# Spannungsversorgung_V4_mitBatze.net
KiCad netlist of a schematic drawn in EAGLE
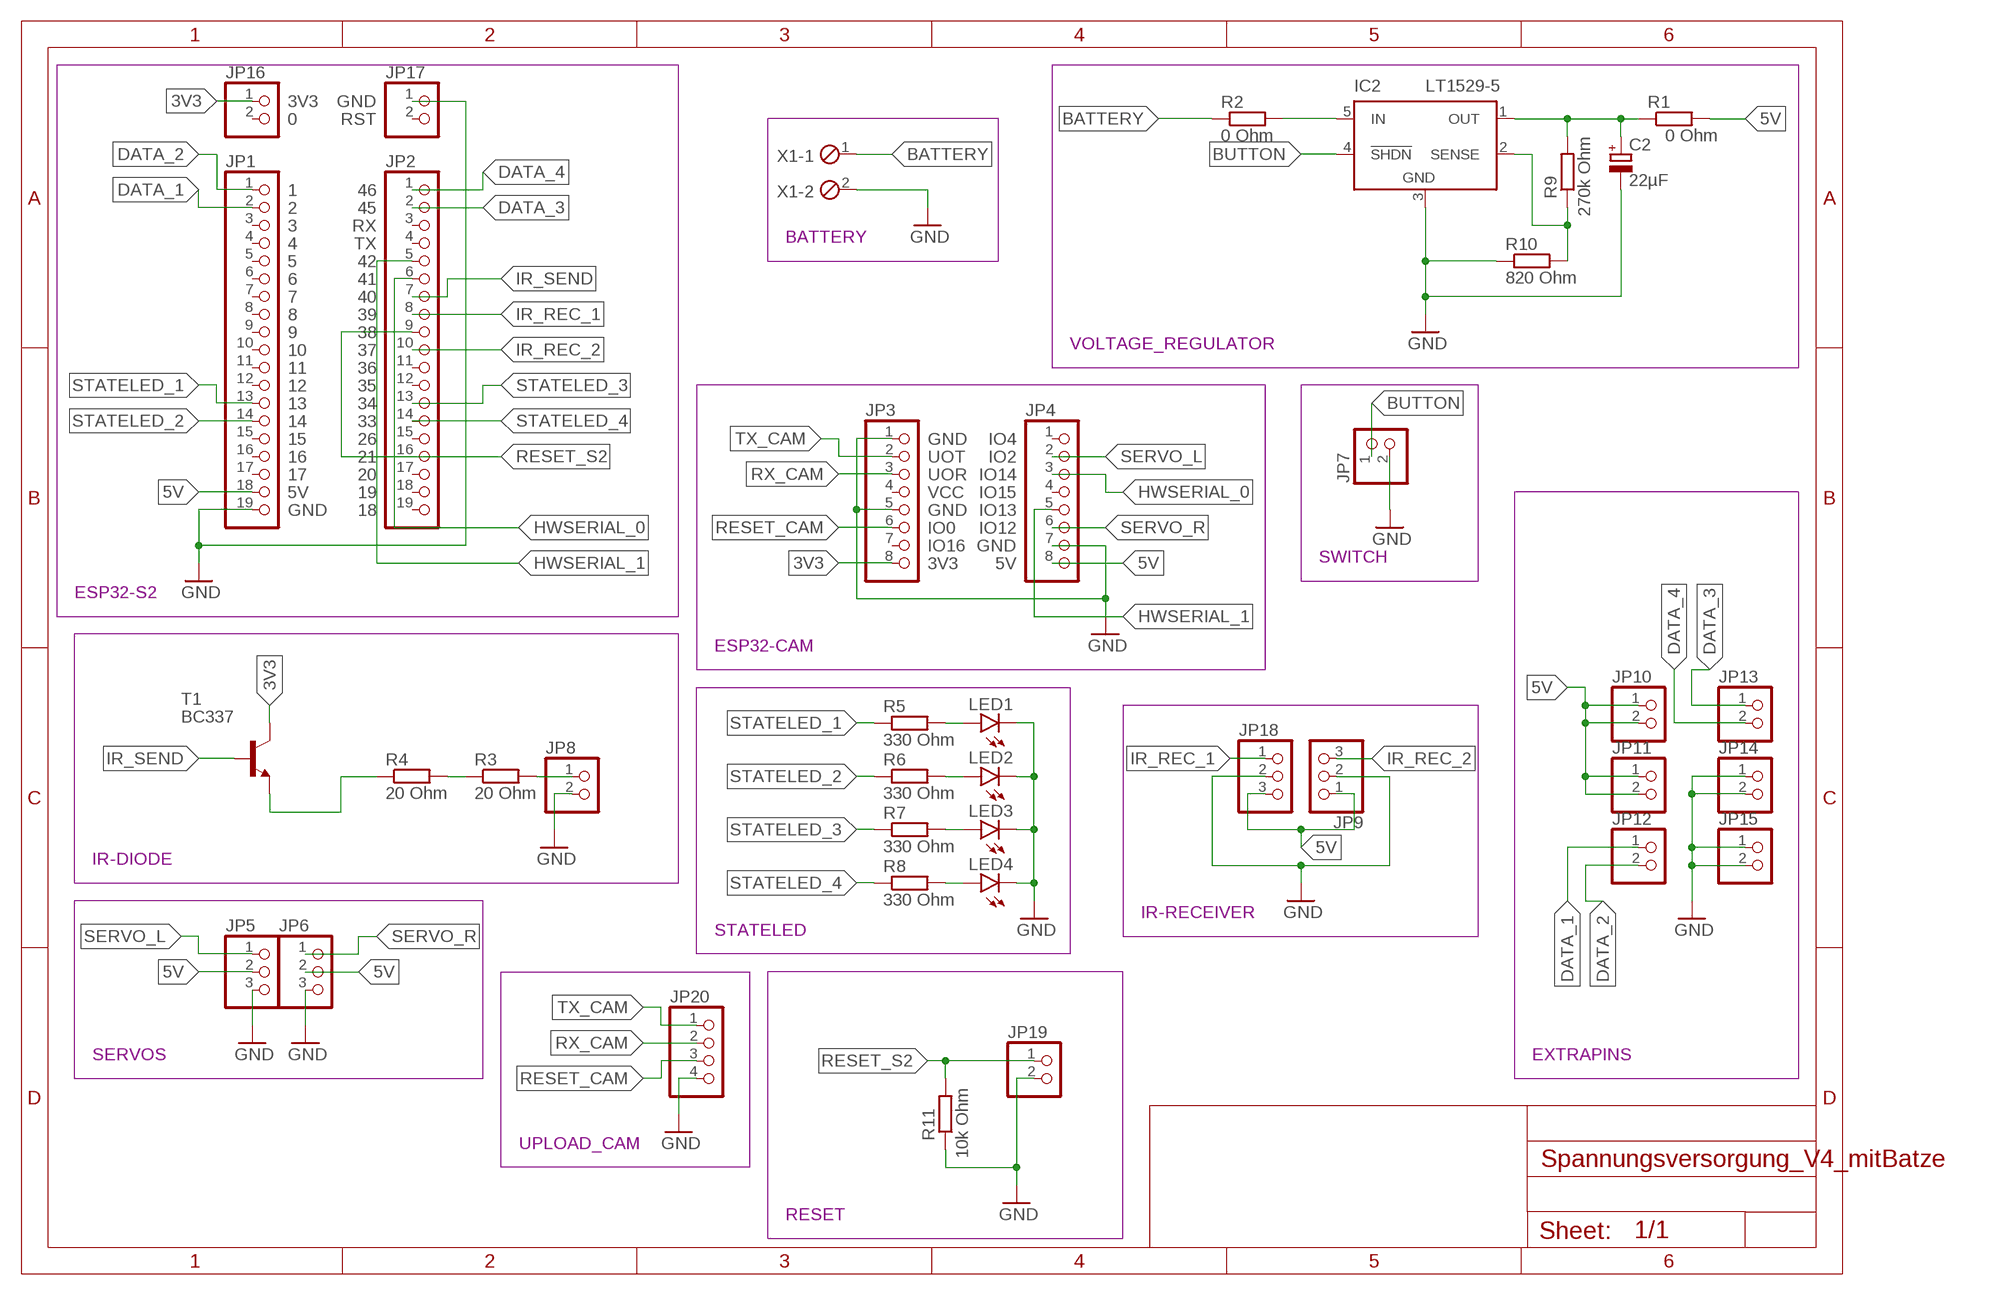
[diagram p0: schematic, sheet 1]

(export (version "E")
  (design (tool "Eeschema 10.0.6"))
  (components
    (comp (ref "C2")
      (value "22µF")
      (footprint "eagle-import:E2,5-5")
      (libsource (lib "eagle-import") (part "CPOL-EUE2.5-5"))
    )
    (comp (ref "IC2")
      (value "LT1529-5")
      (footprint "eagle-import:TO220-5")
      (libsource (lib "eagle-import") (part "LT1529T"))
    )
    (comp (ref "JP1")
      (value "PINHD-1X19")
      (footprint "eagle-import:1X19")
      (libsource (lib "eagle-import") (part "PINHD-1X19"))
    )
    (comp (ref "JP2")
      (value "PINHD-1X19")
      (footprint "eagle-import:1X19")
      (libsource (lib "eagle-import") (part "PINHD-1X19"))
    )
    (comp (ref "JP3")
      (value "PINHD-1X8")
      (footprint "eagle-import:1X08")
      (libsource (lib "eagle-import") (part "PINHD-1X8"))
    )
    (comp (ref "JP4")
      (value "PINHD-1X8")
      (footprint "eagle-import:1X08")
      (libsource (lib "eagle-import") (part "PINHD-1X8"))
    )
    (comp (ref "JP5")
      (value "PINHD-1X3")
      (footprint "eagle-import:1X03")
      (libsource (lib "eagle-import") (part "PINHD-1X3"))
    )
    (comp (ref "JP6")
      (value "PINHD-1X3")
      (footprint "eagle-import:1X03")
      (libsource (lib "eagle-import") (part "PINHD-1X3"))
    )
    (comp (ref "JP7")
      (value "PINHD-1X2")
      (footprint "eagle-import:1X02")
      (libsource (lib "eagle-import") (part "PINHD-1X2"))
    )
    (comp (ref "JP8")
      (value "PINHD-1X2")
      (footprint "eagle-import:1X02")
      (libsource (lib "eagle-import") (part "PINHD-1X2"))
    )
    (comp (ref "JP9")
      (value "PINHD-1X3")
      (footprint "eagle-import:1X03")
      (libsource (lib "eagle-import") (part "PINHD-1X3"))
    )
    (comp (ref "JP10")
      (value "PINHD-1X2")
      (footprint "eagle-import:1X02")
      (libsource (lib "eagle-import") (part "PINHD-1X2"))
    )
    (comp (ref "JP11")
      (value "PINHD-1X2")
      (footprint "eagle-import:1X02")
      (libsource (lib "eagle-import") (part "PINHD-1X2"))
    )
    (comp (ref "JP12")
      (value "PINHD-1X2")
      (footprint "eagle-import:1X02")
      (libsource (lib "eagle-import") (part "PINHD-1X2"))
    )
    (comp (ref "JP13")
      (value "PINHD-1X2")
      (footprint "eagle-import:1X02")
      (libsource (lib "eagle-import") (part "PINHD-1X2"))
    )
    (comp (ref "JP14")
      (value "PINHD-1X2")
      (footprint "eagle-import:1X02")
      (libsource (lib "eagle-import") (part "PINHD-1X2"))
    )
    (comp (ref "JP15")
      (value "PINHD-1X2")
      (footprint "eagle-import:1X02")
      (libsource (lib "eagle-import") (part "PINHD-1X2"))
    )
    (comp (ref "JP16")
      (value "PINHD-1X2")
      (footprint "eagle-import:1X02")
      (libsource (lib "eagle-import") (part "PINHD-1X2"))
    )
    (comp (ref "JP17")
      (value "PINHD-1X2")
      (footprint "eagle-import:1X02")
      (libsource (lib "eagle-import") (part "PINHD-1X2"))
    )
    (comp (ref "JP18")
      (value "PINHD-1X3")
      (footprint "eagle-import:1X03")
      (libsource (lib "eagle-import") (part "PINHD-1X3"))
    )
    (comp (ref "JP19")
      (value "PINHD-1X2")
      (footprint "eagle-import:1X02")
      (libsource (lib "eagle-import") (part "PINHD-1X2"))
    )
    (comp (ref "JP20")
      (value "PINHD-1X4")
      (footprint "eagle-import:1X04")
      (libsource (lib "eagle-import") (part "PINHD-1X4"))
    )
    (comp (ref "LED1")
      (value "LED3MM")
      (footprint "eagle-import:LED3MM")
      (libsource (lib "eagle-import") (part "LED3MM"))
    )
    (comp (ref "LED2")
      (value "LED3MM")
      (footprint "eagle-import:LED3MM")
      (libsource (lib "eagle-import") (part "LED3MM"))
    )
    (comp (ref "LED3")
      (value "LED3MM")
      (footprint "eagle-import:LED3MM")
      (libsource (lib "eagle-import") (part "LED3MM"))
    )
    (comp (ref "LED4")
      (value "LED3MM")
      (footprint "eagle-import:LED3MM")
      (libsource (lib "eagle-import") (part "LED3MM"))
    )
    (comp (ref "R1")
      (value "0 Ohm")
      (footprint "eagle-import:R0805")
      (libsource (lib "eagle-import") (part "R-EU_R0805"))
    )
    (comp (ref "R2")
      (value "0 Ohm")
      (footprint "eagle-import:R0805")
      (libsource (lib "eagle-import") (part "R-EU_R0805"))
    )
    (comp (ref "R3")
      (value "20 Ohm")
      (footprint "eagle-import:0309_12")
      (libsource (lib "eagle-import") (part "R-EU_0309/12"))
    )
    (comp (ref "R4")
      (value "20 Ohm")
      (footprint "eagle-import:0309_12")
      (libsource (lib "eagle-import") (part "R-EU_0309/12"))
    )
    (comp (ref "R5")
      (value "330 Ohm")
      (footprint "eagle-import:R0805")
      (libsource (lib "eagle-import") (part "R-EU_R0805"))
    )
    (comp (ref "R6")
      (value "330 Ohm")
      (footprint "eagle-import:R0805")
      (libsource (lib "eagle-import") (part "R-EU_R0805"))
    )
    (comp (ref "R7")
      (value "330 Ohm")
      (footprint "eagle-import:R0805")
      (libsource (lib "eagle-import") (part "R-EU_R0805"))
    )
    (comp (ref "R8")
      (value "330 Ohm")
      (footprint "eagle-import:R0805")
      (libsource (lib "eagle-import") (part "R-EU_R0805"))
    )
    (comp (ref "R9")
      (value "270k Ohm")
      (footprint "eagle-import:0309_12")
      (libsource (lib "eagle-import") (part "R-EU_0309/12"))
    )
    (comp (ref "R10")
      (value "820 Ohm")
      (footprint "eagle-import:0309_12")
      (libsource (lib "eagle-import") (part "R-EU_0309/12"))
    )
    (comp (ref "R11")
      (value "10k Ohm")
      (footprint "eagle-import:0309_12")
      (libsource (lib "eagle-import") (part "R-EU_0309/12"))
    )
    (comp (ref "T1")
      (value "BC337")
      (footprint "eagle-import:TO92")
      (libsource (lib "eagle-import") (part "BC337"))
    )
    (comp (ref "X1")
      (value "MPT2")
      (footprint "eagle-import:2POL254")
      (libsource (lib "eagle-import") (part "MPT2"))
    )
  )
  (nets
    (net (code "1") (name "3V3") (class "Default")
      (node (ref "JP16") (pin "1") (pinfunction "1_1") (pintype "passive"))
      (node (ref "JP3") (pin "8") (pinfunction "8_8") (pintype "passive"))
      (node (ref "T1") (pin "3") (pinfunction "C_3") (pintype "passive"))
    )
    (net (code "2") (name "5V") (class "Default")
      (node (ref "JP1") (pin "18") (pinfunction "18_18") (pintype "passive"))
      (node (ref "JP10") (pin "1") (pinfunction "1_1") (pintype "passive"))
      (node (ref "JP10") (pin "2") (pinfunction "2_2") (pintype "passive"))
      (node (ref "JP11") (pin "1") (pinfunction "1_1") (pintype "passive"))
      (node (ref "JP11") (pin "2") (pinfunction "2_2") (pintype "passive"))
      (node (ref "JP18") (pin "3") (pinfunction "3_3") (pintype "passive"))
      (node (ref "JP4") (pin "8") (pinfunction "8_8") (pintype "passive"))
      (node (ref "JP5") (pin "2") (pinfunction "2_2") (pintype "passive"))
      (node (ref "JP6") (pin "2") (pinfunction "2_2") (pintype "passive"))
      (node (ref "JP9") (pin "1") (pinfunction "1_1") (pintype "passive"))
      (node (ref "R1") (pin "2") (pinfunction "2_2") (pintype "passive"))
    )
    (net (code "3") (name "BATTERY") (class "Default")
      (node (ref "R2") (pin "1") (pinfunction "1_1") (pintype "passive"))
      (node (ref "X1") (pin "1") (pinfunction "1_1") (pintype "passive"))
    )
    (net (code "4") (name "BUTTON") (class "Default")
      (node (ref "IC2") (pin "4") (pinfunction "~{SHDN}_4") (pintype "input"))
      (node (ref "JP7") (pin "1") (pinfunction "1_1") (pintype "passive"))
    )
    (net (code "5") (name "DATA_1") (class "Default")
      (node (ref "JP1") (pin "2") (pinfunction "2_2") (pintype "passive"))
      (node (ref "JP12") (pin "1") (pinfunction "1_1") (pintype "passive"))
    )
    (net (code "6") (name "DATA_2") (class "Default")
      (node (ref "JP1") (pin "1") (pinfunction "1_1") (pintype "passive"))
      (node (ref "JP12") (pin "2") (pinfunction "2_2") (pintype "passive"))
    )
    (net (code "7") (name "DATA_3") (class "Default")
      (node (ref "JP13") (pin "1") (pinfunction "1_1") (pintype "passive"))
      (node (ref "JP2") (pin "2") (pinfunction "2_2") (pintype "passive"))
    )
    (net (code "8") (name "DATA_4") (class "Default")
      (node (ref "JP13") (pin "2") (pinfunction "2_2") (pintype "passive"))
      (node (ref "JP2") (pin "1") (pinfunction "1_1") (pintype "passive"))
    )
    (net (code "9") (name "GND") (class "Default")
      (node (ref "C2") (pin "-") (pinfunction "-_-") (pintype "passive"))
      (node (ref "IC2") (pin "3") (pinfunction "GND_3") (pintype "power_in"))
      (node (ref "JP1") (pin "19") (pinfunction "19_19") (pintype "passive"))
      (node (ref "JP14") (pin "1") (pinfunction "1_1") (pintype "passive"))
      (node (ref "JP14") (pin "2") (pinfunction "2_2") (pintype "passive"))
      (node (ref "JP15") (pin "1") (pinfunction "1_1") (pintype "passive"))
      (node (ref "JP15") (pin "2") (pinfunction "2_2") (pintype "passive"))
      (node (ref "JP17") (pin "1") (pinfunction "1_1") (pintype "passive"))
      (node (ref "JP18") (pin "2") (pinfunction "2_2") (pintype "passive"))
      (node (ref "JP19") (pin "2") (pinfunction "2_2") (pintype "passive"))
      (node (ref "JP20") (pin "4") (pinfunction "4_4") (pintype "passive"))
      (node (ref "JP3") (pin "1") (pinfunction "1_1") (pintype "passive"))
      (node (ref "JP3") (pin "5") (pinfunction "5_5") (pintype "passive"))
      (node (ref "JP4") (pin "7") (pinfunction "7_7") (pintype "passive"))
      (node (ref "JP5") (pin "3") (pinfunction "3_3") (pintype "passive"))
      (node (ref "JP6") (pin "3") (pinfunction "3_3") (pintype "passive"))
      (node (ref "JP7") (pin "2") (pinfunction "2_2") (pintype "passive"))
      (node (ref "JP8") (pin "2") (pinfunction "2_2") (pintype "passive"))
      (node (ref "JP9") (pin "2") (pinfunction "2_2") (pintype "passive"))
      (node (ref "LED1") (pin "K") (pinfunction "C_K") (pintype "passive"))
      (node (ref "LED2") (pin "K") (pinfunction "C_K") (pintype "passive"))
      (node (ref "LED3") (pin "K") (pinfunction "C_K") (pintype "passive"))
      (node (ref "LED4") (pin "K") (pinfunction "C_K") (pintype "passive"))
      (node (ref "R10") (pin "1") (pinfunction "1_1") (pintype "passive"))
      (node (ref "R11") (pin "1") (pinfunction "1_1") (pintype "passive"))
      (node (ref "X1") (pin "2") (pinfunction "1_2") (pintype "passive"))
    )
    (net (code "10") (name "HWSERIAL_0") (class "Default")
      (node (ref "JP2") (pin "6") (pinfunction "6_6") (pintype "passive"))
      (node (ref "JP4") (pin "3") (pinfunction "3_3") (pintype "passive"))
    )
    (net (code "11") (name "HWSERIAL_1") (class "Default")
      (node (ref "JP2") (pin "5") (pinfunction "5_5") (pintype "passive"))
      (node (ref "JP4") (pin "5") (pinfunction "5_5") (pintype "passive"))
    )
    (net (code "12") (name "IR_REC_1") (class "Default")
      (node (ref "JP18") (pin "1") (pinfunction "1_1") (pintype "passive"))
      (node (ref "JP2") (pin "8") (pinfunction "8_8") (pintype "passive"))
    )
    (net (code "13") (name "IR_REC_2") (class "Default")
      (node (ref "JP2") (pin "10") (pinfunction "10_10") (pintype "passive"))
      (node (ref "JP9") (pin "3") (pinfunction "3_3") (pintype "passive"))
    )
    (net (code "14") (name "IR_SEND") (class "Default")
      (node (ref "JP2") (pin "7") (pinfunction "7_7") (pintype "passive"))
      (node (ref "T1") (pin "2") (pinfunction "B_2") (pintype "passive"))
    )
    (net (code "15") (name "Net-(IC2-IN)") (class "Default")
      (node (ref "IC2") (pin "5") (pinfunction "IN_5") (pintype "input"))
      (node (ref "R2") (pin "2") (pinfunction "2_2") (pintype "passive"))
    )
    (net (code "16") (name "Net-(IC2-OUT)") (class "Default")
      (node (ref "C2") (pin "+") (pinfunction "+_+") (pintype "passive"))
      (node (ref "IC2") (pin "1") (pinfunction "OUT_1") (pintype "output"))
      (node (ref "R1") (pin "1") (pinfunction "1_1") (pintype "passive"))
      (node (ref "R9") (pin "2") (pinfunction "2_2") (pintype "passive"))
    )
    (net (code "17") (name "Net-(IC2-SENSE)") (class "Default")
      (node (ref "IC2") (pin "2") (pinfunction "SENSE_2") (pintype "input"))
      (node (ref "R10") (pin "2") (pinfunction "2_2") (pintype "passive"))
      (node (ref "R9") (pin "1") (pinfunction "1_1") (pintype "passive"))
    )
    (net (code "18") (name "Net-(JP8-Pad1)") (class "Default")
      (node (ref "JP8") (pin "1") (pinfunction "1_1") (pintype "passive"))
      (node (ref "R3") (pin "2") (pinfunction "2_2") (pintype "passive"))
    )
    (net (code "19") (name "Net-(LED1-PadA)") (class "Default")
      (node (ref "LED1") (pin "A") (pinfunction "A_A") (pintype "passive"))
      (node (ref "R5") (pin "2") (pinfunction "2_2") (pintype "passive"))
    )
    (net (code "20") (name "Net-(LED2-PadA)") (class "Default")
      (node (ref "LED2") (pin "A") (pinfunction "A_A") (pintype "passive"))
      (node (ref "R6") (pin "2") (pinfunction "2_2") (pintype "passive"))
    )
    (net (code "21") (name "Net-(LED3-PadA)") (class "Default")
      (node (ref "LED3") (pin "A") (pinfunction "A_A") (pintype "passive"))
      (node (ref "R7") (pin "2") (pinfunction "2_2") (pintype "passive"))
    )
    (net (code "22") (name "Net-(LED4-PadA)") (class "Default")
      (node (ref "LED4") (pin "A") (pinfunction "A_A") (pintype "passive"))
      (node (ref "R8") (pin "2") (pinfunction "2_2") (pintype "passive"))
    )
    (net (code "23") (name "Net-(R3-Pad1)") (class "Default")
      (node (ref "R3") (pin "1") (pinfunction "1_1") (pintype "passive"))
      (node (ref "R4") (pin "2") (pinfunction "2_2") (pintype "passive"))
    )
    (net (code "24") (name "Net-(T1-E)") (class "Default")
      (node (ref "R4") (pin "1") (pinfunction "1_1") (pintype "passive"))
      (node (ref "T1") (pin "1") (pinfunction "E_1") (pintype "passive"))
    )
    (net (code "25") (name "RESET_CAM") (class "Default")
      (node (ref "JP20") (pin "3") (pinfunction "3_3") (pintype "passive"))
      (node (ref "JP3") (pin "6") (pinfunction "6_6") (pintype "passive"))
    )
    (net (code "26") (name "RESET_S2") (class "Default")
      (node (ref "JP19") (pin "1") (pinfunction "1_1") (pintype "passive"))
      (node (ref "JP2") (pin "9") (pinfunction "9_9") (pintype "passive"))
      (node (ref "R11") (pin "2") (pinfunction "2_2") (pintype "passive"))
    )
    (net (code "27") (name "RX_CAM") (class "Default")
      (node (ref "JP20") (pin "2") (pinfunction "2_2") (pintype "passive"))
      (node (ref "JP3") (pin "3") (pinfunction "3_3") (pintype "passive"))
    )
    (net (code "28") (name "SERVO_L") (class "Default")
      (node (ref "JP4") (pin "2") (pinfunction "2_2") (pintype "passive"))
      (node (ref "JP5") (pin "1") (pinfunction "1_1") (pintype "passive"))
    )
    (net (code "29") (name "SERVO_R") (class "Default")
      (node (ref "JP4") (pin "6") (pinfunction "6_6") (pintype "passive"))
      (node (ref "JP6") (pin "1") (pinfunction "1_1") (pintype "passive"))
    )
    (net (code "30") (name "STATELED_1") (class "Default")
      (node (ref "JP1") (pin "13") (pinfunction "13_13") (pintype "passive"))
      (node (ref "R5") (pin "1") (pinfunction "1_1") (pintype "passive"))
    )
    (net (code "31") (name "STATELED_2") (class "Default")
      (node (ref "JP1") (pin "14") (pinfunction "14_14") (pintype "passive"))
      (node (ref "R6") (pin "1") (pinfunction "1_1") (pintype "passive"))
    )
    (net (code "32") (name "STATELED_3") (class "Default")
      (node (ref "JP2") (pin "13") (pinfunction "13_13") (pintype "passive"))
      (node (ref "R7") (pin "1") (pinfunction "1_1") (pintype "passive"))
    )
    (net (code "33") (name "STATELED_4") (class "Default")
      (node (ref "JP2") (pin "14") (pinfunction "14_14") (pintype "passive"))
      (node (ref "R8") (pin "1") (pinfunction "1_1") (pintype "passive"))
    )
    (net (code "34") (name "TX_CAM") (class "Default")
      (node (ref "JP20") (pin "1") (pinfunction "1_1") (pintype "passive"))
      (node (ref "JP3") (pin "2") (pinfunction "2_2") (pintype "passive"))
    )
    (net (code "35") (name "unconnected-(JP1-Pad3)") (class "Default")
      (node (ref "JP1") (pin "3") (pinfunction "3_3") (pintype "passive"))
    )
    (net (code "36") (name "unconnected-(JP1-Pad4)") (class "Default")
      (node (ref "JP1") (pin "4") (pinfunction "4_4") (pintype "passive"))
    )
    (net (code "37") (name "unconnected-(JP1-Pad5)") (class "Default")
      (node (ref "JP1") (pin "5") (pinfunction "5_5") (pintype "passive"))
    )
    (net (code "38") (name "unconnected-(JP1-Pad6)") (class "Default")
      (node (ref "JP1") (pin "6") (pinfunction "6_6") (pintype "passive"))
    )
    (net (code "39") (name "unconnected-(JP1-Pad7)") (class "Default")
      (node (ref "JP1") (pin "7") (pinfunction "7_7") (pintype "passive"))
    )
    (net (code "40") (name "unconnected-(JP1-Pad8)") (class "Default")
      (node (ref "JP1") (pin "8") (pinfunction "8_8") (pintype "passive"))
    )
    (net (code "41") (name "unconnected-(JP1-Pad9)") (class "Default")
      (node (ref "JP1") (pin "9") (pinfunction "9_9") (pintype "passive"))
    )
    (net (code "42") (name "unconnected-(JP1-Pad10)") (class "Default")
      (node (ref "JP1") (pin "10") (pinfunction "10_10") (pintype "passive"))
    )
    (net (code "43") (name "unconnected-(JP1-Pad11)") (class "Default")
      (node (ref "JP1") (pin "11") (pinfunction "11_11") (pintype "passive"))
    )
    (net (code "44") (name "unconnected-(JP1-Pad12)") (class "Default")
      (node (ref "JP1") (pin "12") (pinfunction "12_12") (pintype "passive"))
    )
    (net (code "45") (name "unconnected-(JP1-Pad15)") (class "Default")
      (node (ref "JP1") (pin "15") (pinfunction "15_15") (pintype "passive"))
    )
    (net (code "46") (name "unconnected-(JP1-Pad16)") (class "Default")
      (node (ref "JP1") (pin "16") (pinfunction "16_16") (pintype "passive"))
    )
    (net (code "47") (name "unconnected-(JP1-Pad17)") (class "Default")
      (node (ref "JP1") (pin "17") (pinfunction "17_17") (pintype "passive"))
    )
    (net (code "48") (name "unconnected-(JP2-Pad3)") (class "Default")
      (node (ref "JP2") (pin "3") (pinfunction "3_3") (pintype "passive"))
    )
    (net (code "49") (name "unconnected-(JP2-Pad4)") (class "Default")
      (node (ref "JP2") (pin "4") (pinfunction "4_4") (pintype "passive"))
    )
    (net (code "50") (name "unconnected-(JP2-Pad11)") (class "Default")
      (node (ref "JP2") (pin "11") (pinfunction "11_11") (pintype "passive"))
    )
    (net (code "51") (name "unconnected-(JP2-Pad12)") (class "Default")
      (node (ref "JP2") (pin "12") (pinfunction "12_12") (pintype "passive"))
    )
    (net (code "52") (name "unconnected-(JP2-Pad15)") (class "Default")
      (node (ref "JP2") (pin "15") (pinfunction "15_15") (pintype "passive"))
    )
    (net (code "53") (name "unconnected-(JP2-Pad16)") (class "Default")
      (node (ref "JP2") (pin "16") (pinfunction "16_16") (pintype "passive"))
    )
    (net (code "54") (name "unconnected-(JP2-Pad17)") (class "Default")
      (node (ref "JP2") (pin "17") (pinfunction "17_17") (pintype "passive"))
    )
    (net (code "55") (name "unconnected-(JP2-Pad18)") (class "Default")
      (node (ref "JP2") (pin "18") (pinfunction "18_18") (pintype "passive"))
    )
    (net (code "56") (name "unconnected-(JP2-Pad19)") (class "Default")
      (node (ref "JP2") (pin "19") (pinfunction "19_19") (pintype "passive"))
    )
    (net (code "57") (name "unconnected-(JP3-Pad4)") (class "Default")
      (node (ref "JP3") (pin "4") (pinfunction "4_4") (pintype "passive"))
    )
    (net (code "58") (name "unconnected-(JP3-Pad7)") (class "Default")
      (node (ref "JP3") (pin "7") (pinfunction "7_7") (pintype "passive"))
    )
    (net (code "59") (name "unconnected-(JP4-Pad1)") (class "Default")
      (node (ref "JP4") (pin "1") (pinfunction "1_1") (pintype "passive"))
    )
    (net (code "60") (name "unconnected-(JP4-Pad4)") (class "Default")
      (node (ref "JP4") (pin "4") (pinfunction "4_4") (pintype "passive"))
    )
    (net (code "61") (name "unconnected-(JP16-Pad2)") (class "Default")
      (node (ref "JP16") (pin "2") (pinfunction "2_2") (pintype "passive"))
    )
    (net (code "62") (name "unconnected-(JP17-Pad2)") (class "Default")
      (node (ref "JP17") (pin "2") (pinfunction "2_2") (pintype "passive"))
    )
  )
)
